# Activity_Recognition_Board_v1_0_Sensor.net
KiCad netlist of a schematic drawn in Altium Designer
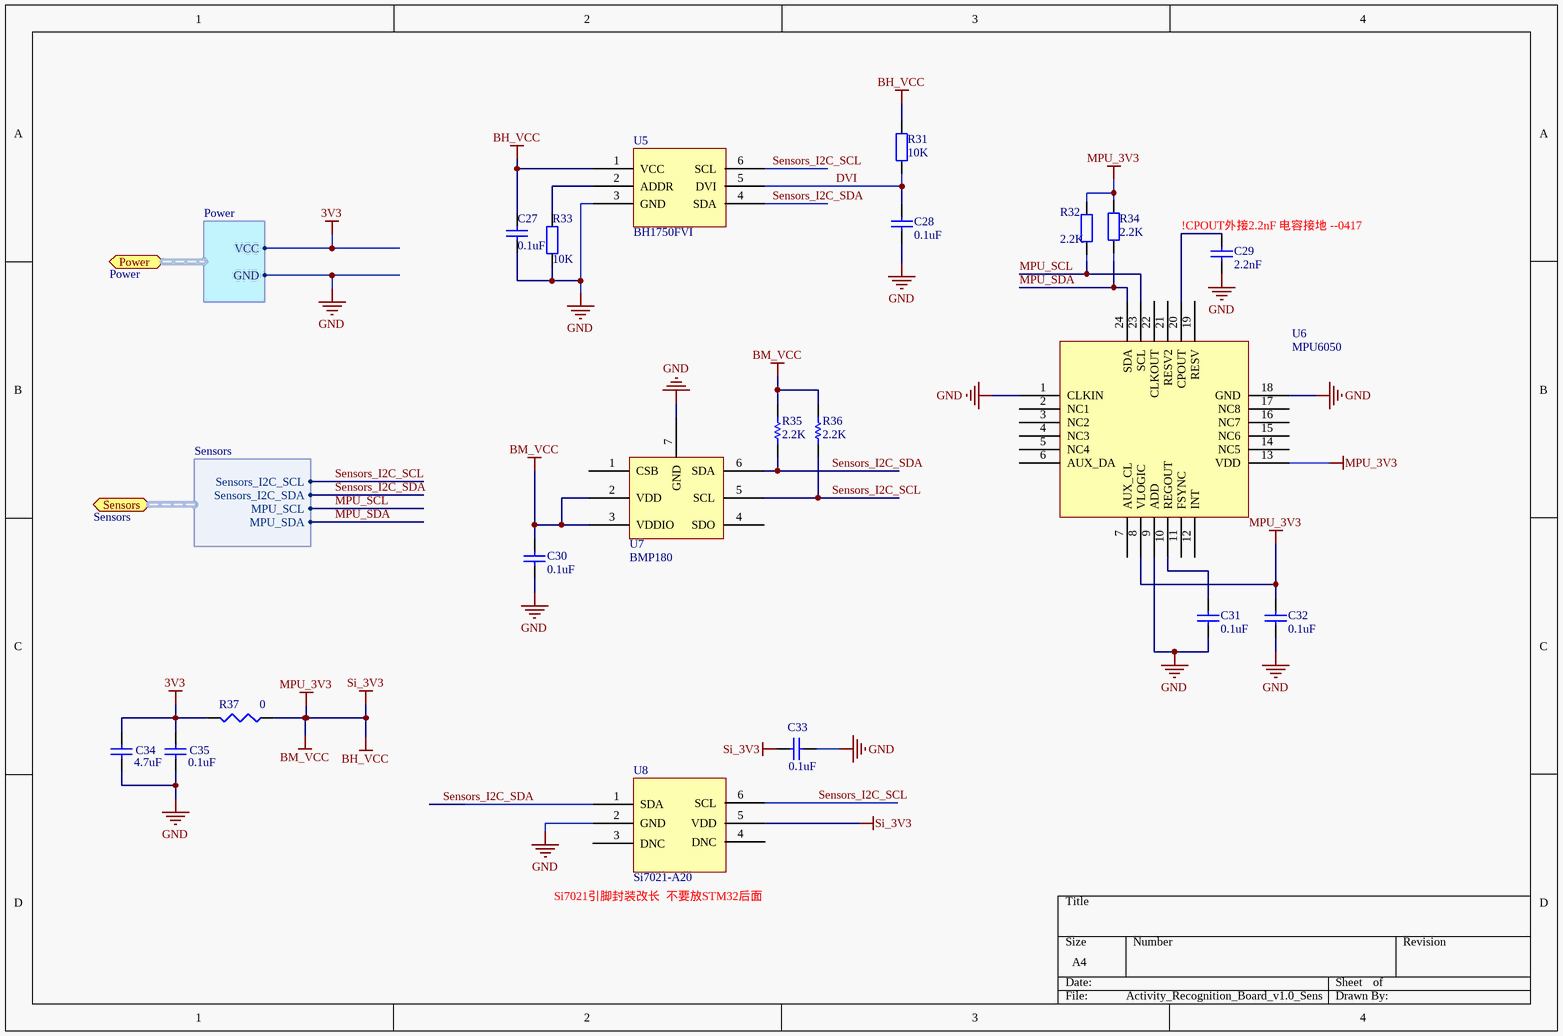
[diagram p0: Activity_Recognition_Board_v1.0_Sensor.SchDoc]

(export (version "E")
  (design (tool "Eeschema 10.0.6"))
  (components
    (comp (ref "C27")
      (value "0.1uF")
      (footprint "C0402")
      (description "Capacitor (Semiconductor SIM Model)")
      (fields (field (name "Comment") "Cap semi") (field (name "PUBLISHER") "Altium Limited"))
      (libsource (lib "Miscellaneous Devices") (part "Cap Semi"))
    )
    (comp (ref "C28")
      (value "0.1uF")
      (footprint "C0402")
      (description "Capacitor (Semiconductor SIM Model)")
      (fields (field (name "Comment") "Cap semi") (field (name "PUBLISHER") "Altium Limited"))
      (libsource (lib "Miscellaneous Devices") (part "Cap Semi"))
    )
    (comp (ref "C29")
      (value "2.2nF")
      (footprint "C0402")
      (description "Capacitor (Semiconductor SIM Model)")
      (fields (field (name "Comment") "Cap semi") (field (name "PUBLISHER") "Altium Limited"))
      (libsource (lib "Miscellaneous Devices") (part "Cap Semi"))
    )
    (comp (ref "C30")
      (value "0.1uF")
      (footprint "C0402")
      (description "Capacitor (Semiconductor SIM Model)")
      (fields (field (name "Comment") "Cap semi") (field (name "PUBLISHER") "Altium Limited"))
      (libsource (lib "Miscellaneous Devices") (part "Cap Semi"))
    )
    (comp (ref "C31")
      (value "0.1uF")
      (footprint "C0402")
      (description "Capacitor (Semiconductor SIM Model)")
      (fields (field (name "Comment") "Cap semi") (field (name "PUBLISHER") "Altium Limited"))
      (libsource (lib "Miscellaneous Devices") (part "Cap Semi"))
    )
    (comp (ref "C32")
      (value "0.1uF")
      (footprint "C0402")
      (description "Capacitor (Semiconductor SIM Model)")
      (fields (field (name "Comment") "Cap semi") (field (name "PUBLISHER") "Altium Limited"))
      (libsource (lib "Miscellaneous Devices") (part "Cap Semi"))
    )
    (comp (ref "C33")
      (value "0.1uF")
      (footprint "C0402")
      (description "Capacitor (Semiconductor SIM Model)")
      (fields (field (name "Comment") "Cap semi") (field (name "PUBLISHER") "Altium Limited"))
      (libsource (lib "Miscellaneous Devices") (part "Cap Semi"))
    )
    (comp (ref "C34")
      (value "4.7uF")
      (footprint "C0603")
      (description "Capacitor (Semiconductor SIM Model)")
      (fields (field (name "Comment") "Cap semi") (field (name "PUBLISHER") "Altium Limited"))
      (libsource (lib "Miscellaneous Devices") (part "Cap Semi"))
    )
    (comp (ref "C35")
      (value "0.1uF")
      (footprint "C0402")
      (description "Capacitor (Semiconductor SIM Model)")
      (fields (field (name "Comment") "Cap semi") (field (name "PUBLISHER") "Altium Limited"))
      (libsource (lib "Miscellaneous Devices") (part "Cap Semi"))
    )
    (comp (ref "R31")
      (value "10K")
      (footprint "R0402")
      (description "Resistor")
      (fields (field (name "Comment") "Res2") (field (name "PUBLISHER") "Altium Limited"))
      (libsource (lib "Miscellaneous Devices") (part "Res2"))
    )
    (comp (ref "R32")
      (value "2.2K")
      (footprint "R0402")
      (description "Resistor")
      (fields (field (name "Comment") "Res2") (field (name "PUBLISHER") "Altium Limited"))
      (libsource (lib "") (part "Res2_1"))
    )
    (comp (ref "R33")
      (value "10K")
      (footprint "R0402")
      (description "Resistor")
      (fields (field (name "Comment") "Res2") (field (name "PUBLISHER") "Altium Limited"))
      (libsource (lib "Miscellaneous Devices") (part "Res2"))
    )
    (comp (ref "R34")
      (value "2.2K")
      (footprint "R0402")
      (description "Resistor")
      (fields (field (name "Comment") "Res2") (field (name "PUBLISHER") "Altium Limited"))
      (libsource (lib "") (part "Res2_1"))
    )
    (comp (ref "R35")
      (value "2.2K")
      (footprint "R0402")
      (description "Resistor")
      (fields (field (name "Comment") "Res1") (field (name "PUBLISHER") "Altium Limited"))
      (libsource (lib "Miscellaneous Devices") (part "Res1"))
    )
    (comp (ref "R36")
      (value "2.2K")
      (footprint "R0402")
      (description "Resistor")
      (fields (field (name "Comment") "Res1") (field (name "PUBLISHER") "Altium Limited"))
      (libsource (lib "Miscellaneous Devices") (part "Res1"))
    )
    (comp (ref "R37")
      (value "0")
      (footprint "R0402")
      (description "Resistor")
      (fields (field (name "Comment") "Res3") (field (name "PUBLISHER") "Altium Limited"))
      (libsource (lib "Miscellaneous Devices") (part "Res3"))
    )
    (comp (ref "U5")
      (value "BH1750FVI")
      (footprint "WSOF6I")
      (libsource (lib "Schlib1_GuJun") (part "BH1750FVI"))
    )
    (comp (ref "U6")
      (value "MPU6050")
      (footprint "QFN-24")
      (libsource (lib "Schlib1_GuJun") (part "MPU6050"))
    )
    (comp (ref "U7")
      (value "BMP180")
      (footprint "LGA7")
      (libsource (lib "Activity_Recognition_Board") (part "BMP180"))
    )
    (comp (ref "U8")
      (value "Si7021-A20")
      (footprint "Si7021-A10")
      (libsource (lib "Schlib1_GuJun") (part "Si7021-A20"))
    )
  )
  (nets
    (net (code "3") (name "/DVI") (class "Default")
      (node (ref "C28") (pin "2") (pinfunction "2_2") (pintype "passive"))
      (node (ref "R31") (pin "2") (pinfunction "2_2") (pintype "passive"))
      (node (ref "U5") (pin "5") (pinfunction "DVI_5") (pintype "passive"))
    )
    (net (code "4") (name "/MPU_SCL") (class "Default")
      (node (ref "R32") (pin "1") (pinfunction "1_1") (pintype "passive"))
      (node (ref "U6") (pin "23") (pinfunction "SCL_23") (pintype "passive"))
    )
    (net (code "5") (name "/MPU_SDA") (class "Default")
      (node (ref "R34") (pin "1") (pinfunction "1_1") (pintype "passive"))
      (node (ref "U6") (pin "24") (pinfunction "SDA_24") (pintype "passive"))
    )
    (net (code "6") (name "/Sensors_I2C_SCL") (class "Default")
      (node (ref "R36") (pin "1") (pinfunction "1_1") (pintype "passive"))
      (node (ref "U5") (pin "6") (pinfunction "SCL_6") (pintype "passive"))
      (node (ref "U7") (pin "5") (pinfunction "SCL_5") (pintype "passive"))
      (node (ref "U8") (pin "6") (pinfunction "SCL_6") (pintype "passive"))
    )
    (net (code "7") (name "/Sensors_I2C_SDA") (class "Default")
      (node (ref "R35") (pin "1") (pinfunction "1_1") (pintype "passive"))
      (node (ref "U5") (pin "4") (pinfunction "SDA_4") (pintype "passive"))
      (node (ref "U7") (pin "6") (pinfunction "SDA_6") (pintype "passive"))
      (node (ref "U8") (pin "1") (pinfunction "SDA_1") (pintype "passive"))
    )
    (net (code "11") (name "3V3") (class "Default")
      (node (ref "C34") (pin "1") (pinfunction "1_1") (pintype "passive"))
      (node (ref "C35") (pin "1") (pinfunction "1_1") (pintype "passive"))
      (node (ref "R37") (pin "2") (pinfunction "2_2") (pintype "passive"))
    )
    (net (code "12") (name "BH_VCC") (class "Default")
      (node (ref "C27") (pin "2") (pinfunction "2_2") (pintype "passive"))
      (node (ref "C30") (pin "2") (pinfunction "2_2") (pintype "passive"))
      (node (ref "C32") (pin "1") (pinfunction "1_1") (pintype "passive"))
      (node (ref "C33") (pin "2") (pinfunction "2_2") (pintype "passive"))
      (node (ref "R31") (pin "1") (pinfunction "1_1") (pintype "passive"))
      (node (ref "R32") (pin "2") (pinfunction "2_2") (pintype "passive"))
      (node (ref "R34") (pin "2") (pinfunction "2_2") (pintype "passive"))
      (node (ref "R35") (pin "2") (pinfunction "2_2") (pintype "passive"))
      (node (ref "R36") (pin "2") (pinfunction "2_2") (pintype "passive"))
      (node (ref "R37") (pin "1") (pinfunction "1_1") (pintype "passive"))
      (node (ref "U5") (pin "1") (pinfunction "VCC_1") (pintype "passive"))
      (node (ref "U6") (pin "13") (pinfunction "VDD_13") (pintype "passive"))
      (node (ref "U6") (pin "8") (pinfunction "VLOGIC_8") (pintype "passive"))
      (node (ref "U7") (pin "2") (pinfunction "VDD_2") (pintype "passive"))
      (node (ref "U7") (pin "3") (pinfunction "VDDIO_3") (pintype "passive"))
      (node (ref "U8") (pin "5") (pinfunction "VDD_5") (pintype "passive"))
    )
    (net (code "13") (name "GND") (class "Default")
      (node (ref "C27") (pin "1") (pinfunction "1_1") (pintype "passive"))
      (node (ref "C28") (pin "1") (pinfunction "1_1") (pintype "passive"))
      (node (ref "C29") (pin "2") (pinfunction "2_2") (pintype "passive"))
      (node (ref "C30") (pin "1") (pinfunction "1_1") (pintype "passive"))
      (node (ref "C31") (pin "2") (pinfunction "2_2") (pintype "passive"))
      (node (ref "C32") (pin "2") (pinfunction "2_2") (pintype "passive"))
      (node (ref "C33") (pin "1") (pinfunction "1_1") (pintype "passive"))
      (node (ref "C34") (pin "2") (pinfunction "2_2") (pintype "passive"))
      (node (ref "C35") (pin "2") (pinfunction "2_2") (pintype "passive"))
      (node (ref "R33") (pin "2") (pinfunction "2_2") (pintype "passive"))
      (node (ref "U5") (pin "3") (pinfunction "GND_3") (pintype "passive"))
      (node (ref "U6") (pin "1") (pinfunction "CLKIN_1") (pintype "passive"))
      (node (ref "U6") (pin "18") (pinfunction "GND_18") (pintype "passive"))
      (node (ref "U6") (pin "9") (pinfunction "ADD_9") (pintype "passive"))
      (node (ref "U7") (pin "7") (pinfunction "GND_7") (pintype "passive"))
      (node (ref "U8") (pin "2") (pinfunction "GND_2") (pintype "passive"))
    )
    (net (code "14") (name "Net-(U5-ADDR)") (class "Default")
      (node (ref "R33") (pin "1") (pinfunction "1_1") (pintype "passive"))
      (node (ref "U5") (pin "2") (pinfunction "ADDR_2") (pintype "passive"))
    )
    (net (code "15") (name "Net-(U6-CPOUT)") (class "Default")
      (node (ref "C29") (pin "1") (pinfunction "1_1") (pintype "passive"))
      (node (ref "U6") (pin "20") (pinfunction "CPOUT_20") (pintype "passive"))
    )
    (net (code "16") (name "Net-(U6-REGOUT)") (class "Default")
      (node (ref "C31") (pin "1") (pinfunction "1_1") (pintype "passive"))
      (node (ref "U6") (pin "10") (pinfunction "REGOUT_10") (pintype "passive"))
    )
    (net (code "17") (name "unconnected-(U6-AUX_CL-Pad7)") (class "Default")
      (node (ref "U6") (pin "7") (pinfunction "AUX_CL_7") (pintype "passive"))
    )
    (net (code "18") (name "unconnected-(U6-AUX_DA-Pad6)") (class "Default")
      (node (ref "U6") (pin "6") (pinfunction "AUX_DA_6") (pintype "passive"))
    )
    (net (code "19") (name "unconnected-(U6-CLKOUT-Pad22)") (class "Default")
      (node (ref "U6") (pin "22") (pinfunction "CLKOUT_22") (pintype "passive"))
    )
    (net (code "20") (name "unconnected-(U6-FSYNC-Pad11)") (class "Default")
      (node (ref "U6") (pin "11") (pinfunction "FSYNC_11") (pintype "passive"))
    )
    (net (code "21") (name "unconnected-(U6-INT-Pad12)") (class "Default")
      (node (ref "U6") (pin "12") (pinfunction "INT_12") (pintype "passive"))
    )
    (net (code "22") (name "unconnected-(U6-NC1-Pad2)") (class "Default")
      (node (ref "U6") (pin "2") (pinfunction "NC1_2") (pintype "passive"))
    )
    (net (code "23") (name "unconnected-(U6-NC2-Pad3)") (class "Default")
      (node (ref "U6") (pin "3") (pinfunction "NC2_3") (pintype "passive"))
    )
    (net (code "24") (name "unconnected-(U6-NC3-Pad4)") (class "Default")
      (node (ref "U6") (pin "4") (pinfunction "NC3_4") (pintype "passive"))
    )
    (net (code "25") (name "unconnected-(U6-NC4-Pad5)") (class "Default")
      (node (ref "U6") (pin "5") (pinfunction "NC4_5") (pintype "passive"))
    )
    (net (code "26") (name "unconnected-(U6-NC5-Pad14)") (class "Default")
      (node (ref "U6") (pin "14") (pinfunction "NC5_14") (pintype "passive"))
    )
    (net (code "27") (name "unconnected-(U6-NC6-Pad15)") (class "Default")
      (node (ref "U6") (pin "15") (pinfunction "NC6_15") (pintype "passive"))
    )
    (net (code "28") (name "unconnected-(U6-NC7-Pad16)") (class "Default")
      (node (ref "U6") (pin "16") (pinfunction "NC7_16") (pintype "passive"))
    )
    (net (code "29") (name "unconnected-(U6-NC8-Pad17)") (class "Default")
      (node (ref "U6") (pin "17") (pinfunction "NC8_17") (pintype "passive"))
    )
    (net (code "30") (name "unconnected-(U6-RESV-Pad19)") (class "Default")
      (node (ref "U6") (pin "19") (pinfunction "RESV_19") (pintype "passive"))
    )
    (net (code "31") (name "unconnected-(U6-RESV2-Pad21)") (class "Default")
      (node (ref "U6") (pin "21") (pinfunction "RESV2_21") (pintype "passive"))
    )
    (net (code "32") (name "unconnected-(U7-CSB-Pad1)") (class "Default")
      (node (ref "U7") (pin "1") (pinfunction "CSB_1") (pintype "passive"))
    )
    (net (code "33") (name "unconnected-(U7-SDO-Pad4)") (class "Default")
      (node (ref "U7") (pin "4") (pinfunction "SDO_4") (pintype "passive"))
    )
    (net (code "34") (name "unconnected-(U8-DNC-Pad3)") (class "Default")
      (node (ref "U8") (pin "3") (pinfunction "DNC_3") (pintype "passive"))
    )
    (net (code "35") (name "unconnected-(U8-DNC-Pad4)") (class "Default")
      (node (ref "U8") (pin "4") (pinfunction "DNC_4") (pintype "passive"))
    )
  )
)
